# main.net
KiCad netlist of a schematic drawn in Altium Designer
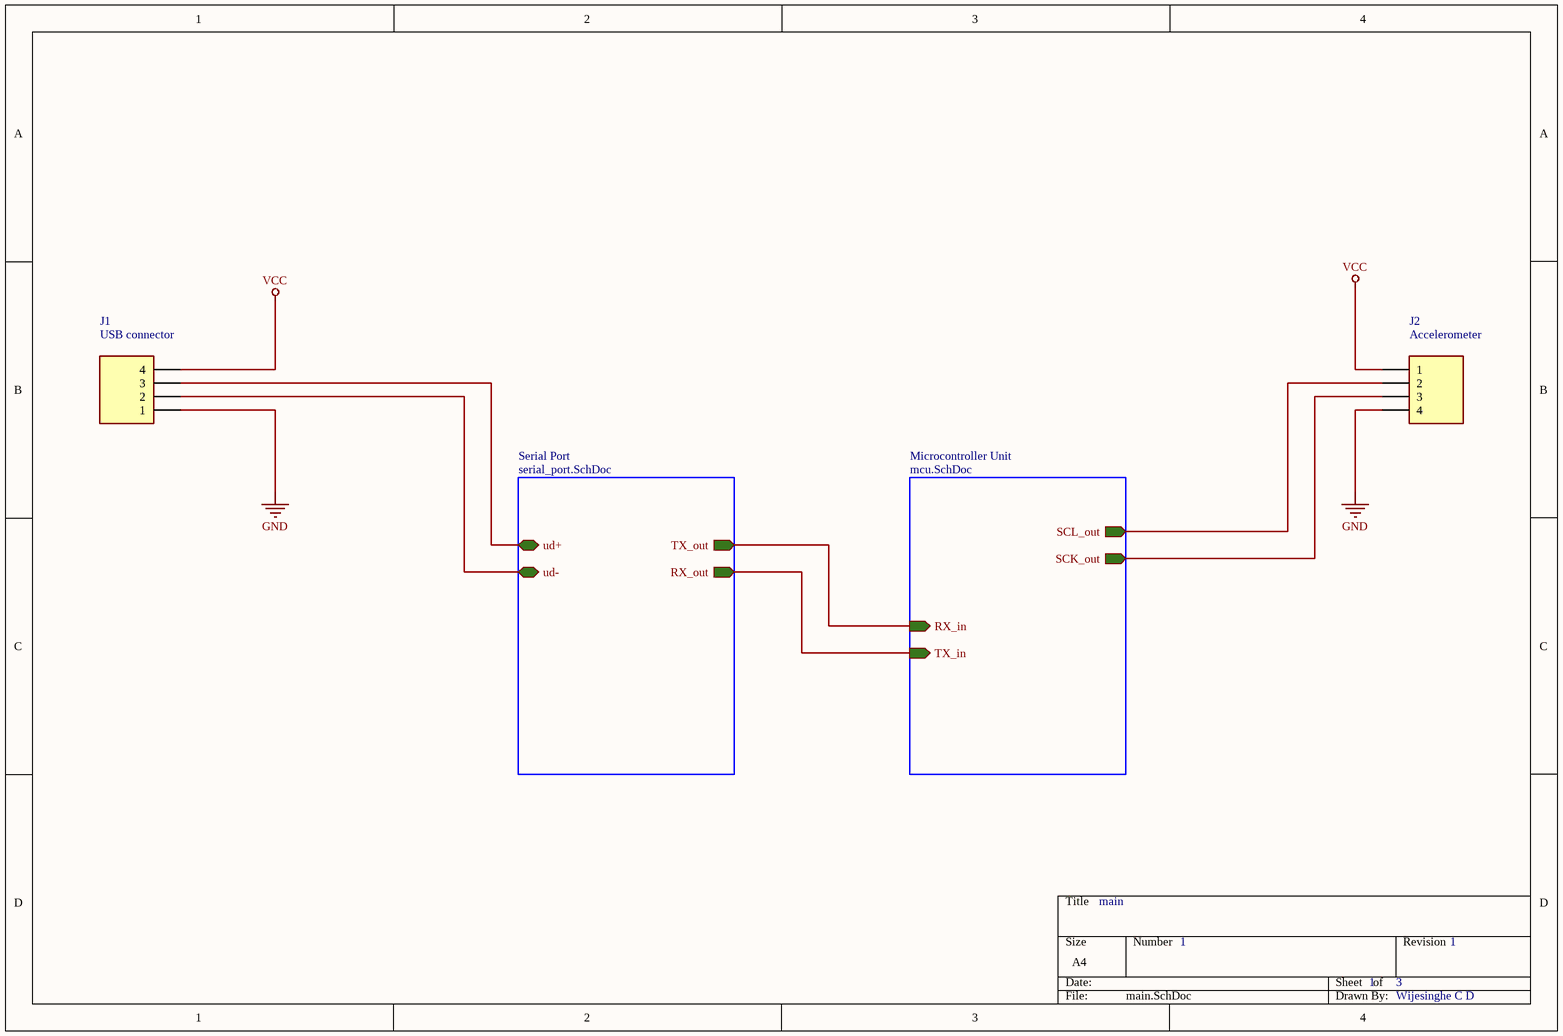
[diagram p0: main.SchDoc]

(export (version "E")
  (design (tool "Eeschema 10.0.6"))
  (components
    (comp (ref "J1")
      (value "USB connector")
      (footprint "SamacSys:B04BPSILEA1LFSN")
      (description "Connector")
      (fields (field (name "MANUFACTURER_PART_NUMBER") "B04B-PSILE-A1(LF)(SN)"))
      (libsource (lib "") (part "B04B-PSILE-A1_LF__SN__1"))
    )
    (comp (ref "J2")
      (value "Accelerometer")
      (footprint "SamacSys:B04BPSILEA1LFSN")
      (description "Connector")
      (fields (field (name "MANUFACTURER_PART_NUMBER") "B04B-PSILE-A1(LF)(SN)"))
      (libsource (lib "*") (part "B04B-PSILE-A1_LF__SN_"))
    )
  )
  (nets
    (net (code "2") (name "/SCK_out") (class "Default")
      (node (ref "J2") (pin "3") (pinfunction "3_3") (pintype "passive"))
    )
    (net (code "3") (name "/SCL_out") (class "Default")
      (node (ref "J2") (pin "2") (pinfunction "2_2") (pintype "passive"))
    )
    (net (code "5") (name "/ud+") (class "Default")
      (node (ref "J1") (pin "3") (pinfunction "3_3") (pintype "passive"))
    )
    (net (code "6") (name "/ud-") (class "Default")
      (node (ref "J1") (pin "2") (pinfunction "2_2") (pintype "passive"))
    )
    (net (code "7") (name "GND") (class "Default")
      (node (ref "J1") (pin "1") (pinfunction "1_1") (pintype "passive"))
      (node (ref "J2") (pin "4") (pinfunction "4_4") (pintype "passive"))
    )
    (net (code "8") (name "VCC") (class "Default")
      (node (ref "J1") (pin "4") (pinfunction "4_4") (pintype "passive"))
      (node (ref "J2") (pin "1") (pinfunction "1_1") (pintype "passive"))
    )
  )
)
